# buck.net
KiCad netlist of a schematic drawn in Altium Designer
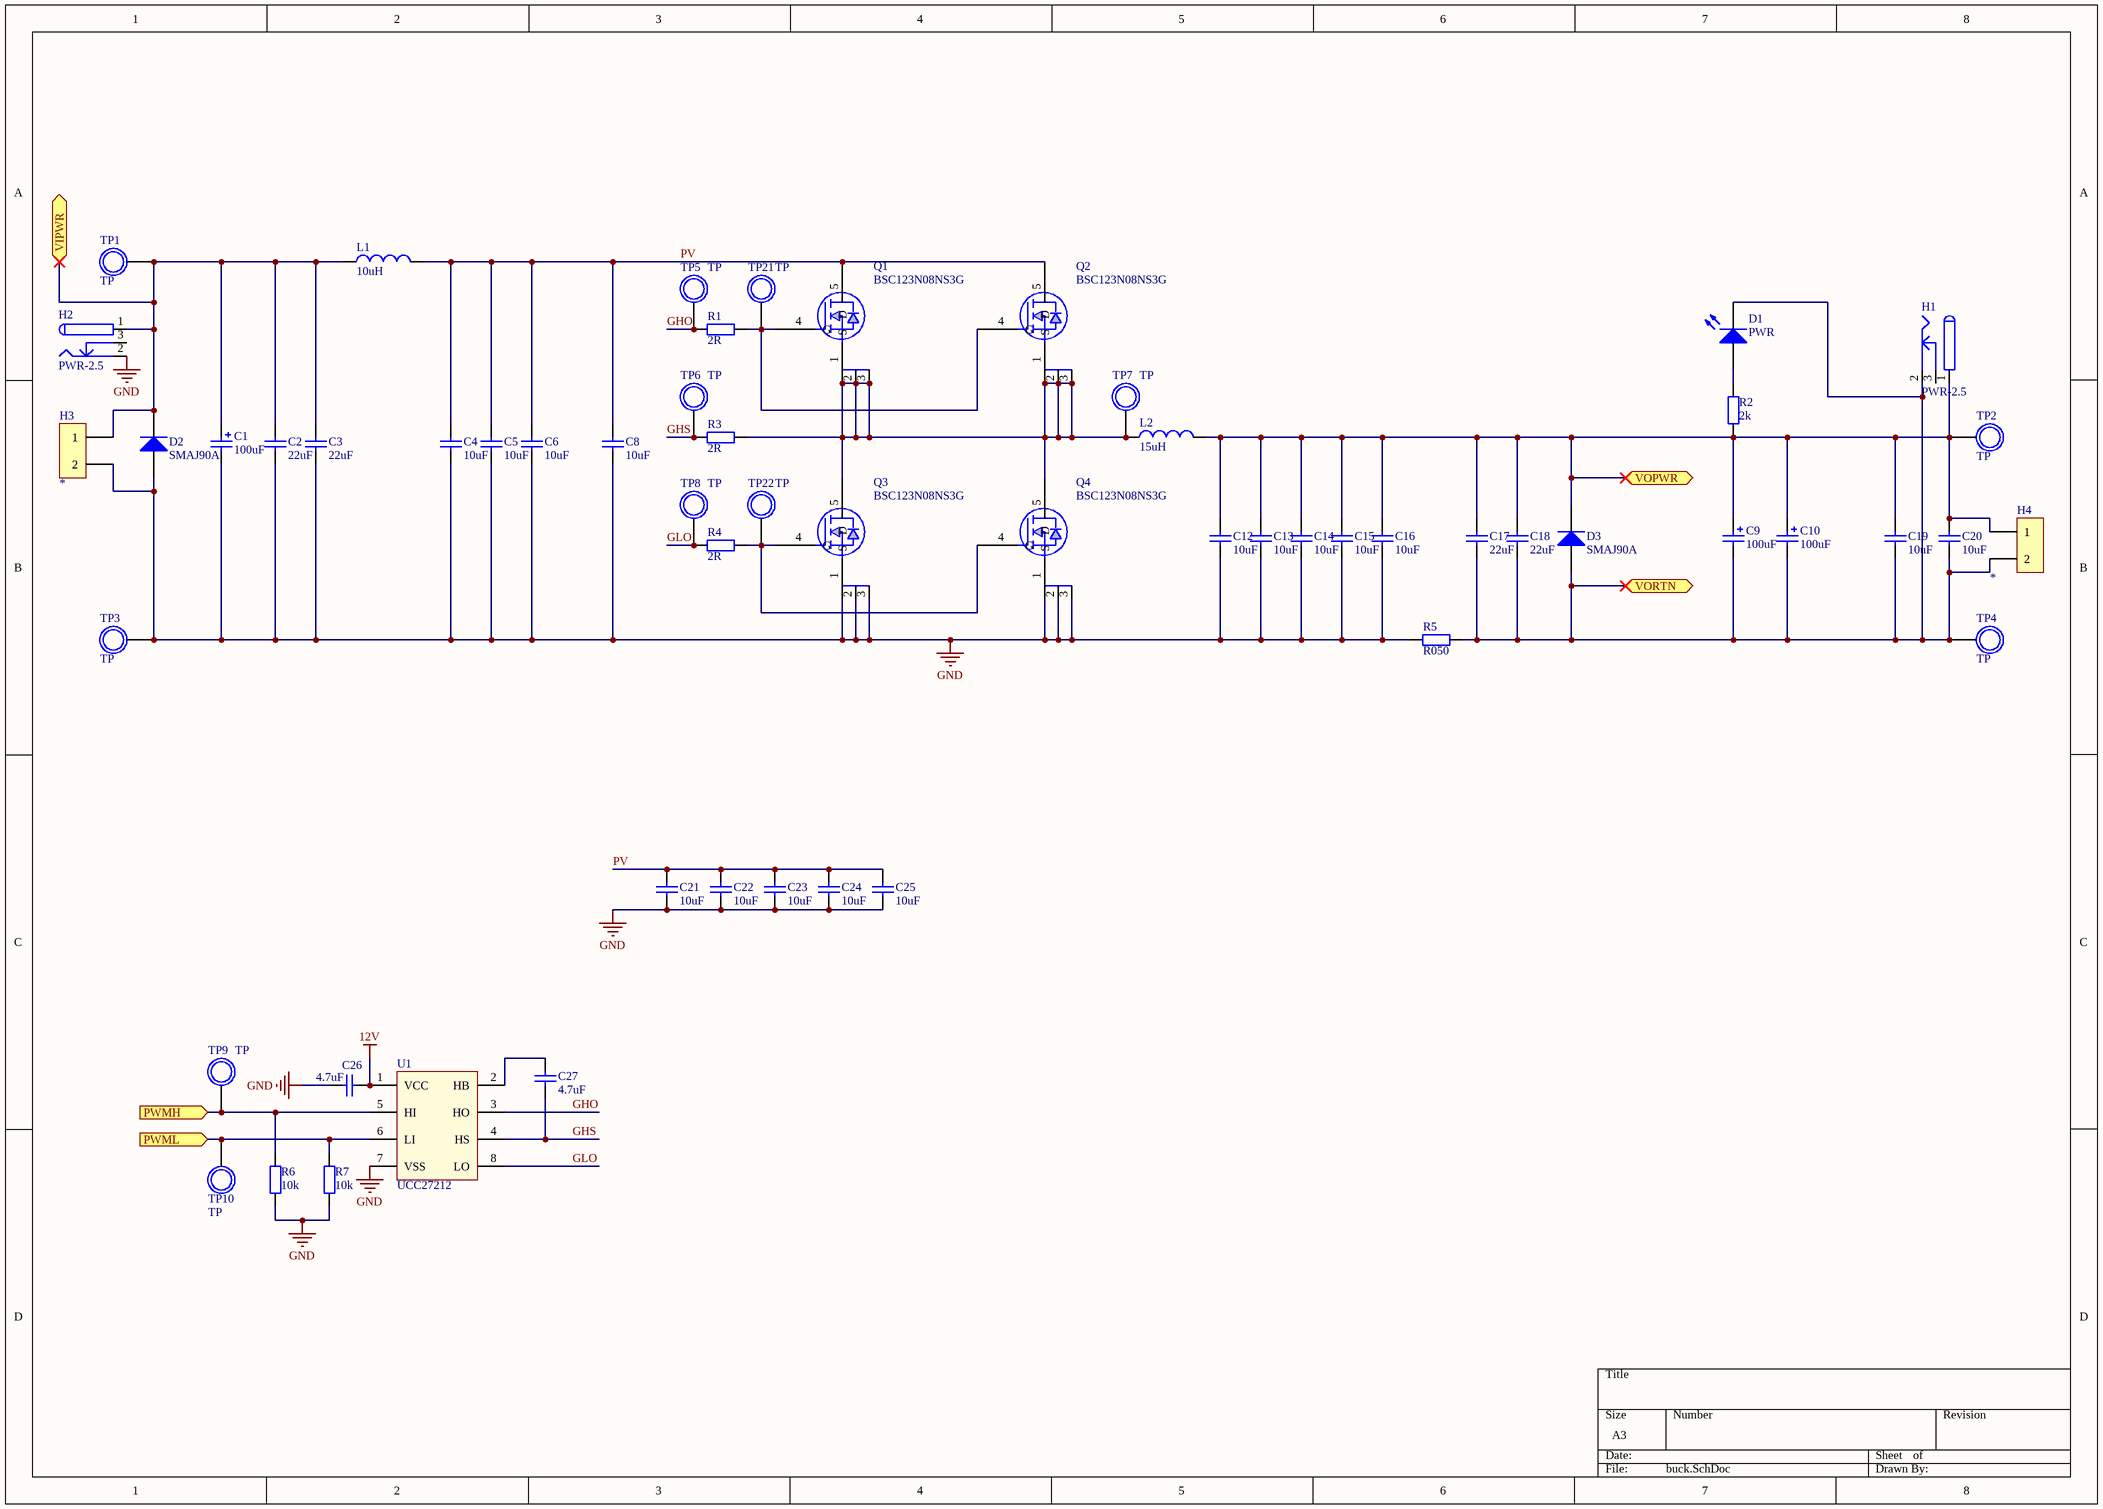
[diagram p0: buck.SchDoc]

(export (version "E")
  (design (tool "Eeschema 10.0.6"))
  (components
    (comp (ref "C1")
      (value "100uF")
      (footprint "CAPAE109103X105N")
      (description "cap pol")
      (fields (field (name "TOLERANCE") "~{+}- 10%"))
      (libsource (lib "PCB_Project") (part "CAP_Pol"))
    )
    (comp (ref "C2")
      (value "22uF")
      (footprint "CAP1206")
      (description "CAP NON-POL")
      (fields (field (name "TOLERANCE") "+/-10%"))
      (libsource (lib "PCB_Project") (part "CAP"))
    )
    (comp (ref "C3")
      (value "22uF")
      (footprint "CAP1206")
      (description "CAP NON-POL")
      (fields (field (name "TOLERANCE") "+/-10%"))
      (libsource (lib "PCB_Project") (part "CAP"))
    )
    (comp (ref "C4")
      (value "10uF")
      (footprint "CAP1206")
      (description "CAP NON-POL")
      (fields (field (name "TOLERANCE") "+/-10%"))
      (libsource (lib "PCB_Project") (part "CAP"))
    )
    (comp (ref "C5")
      (value "10uF")
      (footprint "CAP1206")
      (description "CAP NON-POL")
      (fields (field (name "TOLERANCE") "+/-10%"))
      (libsource (lib "PCB_Project") (part "CAP"))
    )
    (comp (ref "C6")
      (value "10uF")
      (footprint "CAP1206")
      (description "CAP NON-POL")
      (fields (field (name "TOLERANCE") "+/-10%"))
      (libsource (lib "PCB_Project") (part "CAP"))
    )
    (comp (ref "C8")
      (value "10uF")
      (footprint "CAP1206")
      (description "CAP NON-POL")
      (fields (field (name "TOLERANCE") "+/-10%"))
      (libsource (lib "PCB_Project") (part "CAP"))
    )
    (comp (ref "C9")
      (value "100uF")
      (footprint "CAPAE109103X105N")
      (description "cap pol")
      (fields (field (name "TOLERANCE") "~{+}- 10%"))
      (libsource (lib "PCB_Project") (part "CAP_Pol"))
    )
    (comp (ref "C10")
      (value "100uF")
      (footprint "CAPAE109103X105N")
      (description "cap pol")
      (fields (field (name "TOLERANCE") "~{+}- 10%"))
      (libsource (lib "PCB_Project") (part "CAP_Pol"))
    )
    (comp (ref "C12")
      (value "10uF")
      (footprint "CAP1206")
      (description "CAP NON-POL")
      (fields (field (name "TOLERANCE") "+/-10%"))
      (libsource (lib "PCB_Project") (part "CAP"))
    )
    (comp (ref "C13")
      (value "10uF")
      (footprint "CAP1206")
      (description "CAP NON-POL")
      (fields (field (name "TOLERANCE") "+/-10%"))
      (libsource (lib "PCB_Project") (part "CAP"))
    )
    (comp (ref "C14")
      (value "10uF")
      (footprint "CAP1206")
      (description "CAP NON-POL")
      (fields (field (name "TOLERANCE") "+/-10%"))
      (libsource (lib "PCB_Project") (part "CAP"))
    )
    (comp (ref "C15")
      (value "10uF")
      (footprint "CAP1206")
      (description "CAP NON-POL")
      (fields (field (name "TOLERANCE") "+/-10%"))
      (libsource (lib "PCB_Project") (part "CAP"))
    )
    (comp (ref "C16")
      (value "10uF")
      (footprint "CAP1206")
      (description "CAP NON-POL")
      (fields (field (name "TOLERANCE") "+/-10%"))
      (libsource (lib "PCB_Project") (part "CAP"))
    )
    (comp (ref "C17")
      (value "22uF")
      (footprint "CAP1206")
      (description "CAP NON-POL")
      (fields (field (name "TOLERANCE") "+/-10%"))
      (libsource (lib "PCB_Project") (part "CAP"))
    )
    (comp (ref "C18")
      (value "22uF")
      (footprint "CAP1206")
      (description "CAP NON-POL")
      (fields (field (name "TOLERANCE") "+/-10%"))
      (libsource (lib "PCB_Project") (part "CAP"))
    )
    (comp (ref "C19")
      (value "10uF")
      (footprint "CAP1206")
      (description "CAP NON-POL")
      (fields (field (name "TOLERANCE") "+/-10%"))
      (libsource (lib "PCB_Project") (part "CAP"))
    )
    (comp (ref "C20")
      (value "10uF")
      (footprint "CAP1206")
      (description "CAP NON-POL")
      (fields (field (name "TOLERANCE") "+/-10%"))
      (libsource (lib "PCB_Project") (part "CAP"))
    )
    (comp (ref "C21")
      (value "10uF")
      (footprint "CAP1206")
      (description "CAP NON-POL")
      (fields (field (name "TOLERANCE") "+/-10%"))
      (libsource (lib "PCB_Project") (part "CAP"))
    )
    (comp (ref "C22")
      (value "10uF")
      (footprint "CAP1206")
      (description "CAP NON-POL")
      (fields (field (name "TOLERANCE") "+/-10%"))
      (libsource (lib "PCB_Project") (part "CAP"))
    )
    (comp (ref "C23")
      (value "10uF")
      (footprint "CAP1206")
      (description "CAP NON-POL")
      (fields (field (name "TOLERANCE") "+/-10%"))
      (libsource (lib "PCB_Project") (part "CAP"))
    )
    (comp (ref "C24")
      (value "10uF")
      (footprint "CAP1206")
      (description "CAP NON-POL")
      (fields (field (name "TOLERANCE") "+/-10%"))
      (libsource (lib "PCB_Project") (part "CAP"))
    )
    (comp (ref "C25")
      (value "10uF")
      (footprint "CAP1206")
      (description "CAP NON-POL")
      (fields (field (name "TOLERANCE") "+/-10%"))
      (libsource (lib "PCB_Project") (part "CAP"))
    )
    (comp (ref "C26")
      (value "4.7uF")
      (footprint "CAP1206")
      (description "CAP NON-POL")
      (fields (field (name "TOLERANCE") "+/-10%"))
      (libsource (lib "PCB_Project") (part "CAP"))
    )
    (comp (ref "C27")
      (value "4.7uF")
      (footprint "CAP1206")
      (description "CAP NON-POL")
      (fields (field (name "TOLERANCE") "+/-10%"))
      (libsource (lib "PCB_Project") (part "CAP"))
    )
    (comp (ref "D1")
      (value "PWR")
      (footprint "LED0603")
      (description "led")
      (libsource (lib "PCB_Project") (part "LED"))
    )
    (comp (ref "D2")
      (value "SMAJ90A")
      (footprint "SMA")
      (description "diode")
      (libsource (lib "PCB_Project") (part "Diode"))
    )
    (comp (ref "D3")
      (value "SMAJ90A")
      (footprint "SMA")
      (description "diode")
      (libsource (lib "PCB_Project") (part "Diode"))
    )
    (comp (ref "H1") (value "PWR-2.5") (footprint "PWR-2.5") (libsource (lib "PCB_Project") (part "PWR-2.5")))
    (comp (ref "H2") (value "PWR-2.5") (footprint "PWR-2.5") (libsource (lib "PCB_Project") (part "PWR-2.5")))
    (comp (ref "H3") (value "*") (footprint "KF301") (libsource (lib "PCB_Project") (part "Connector-2P")))
    (comp (ref "H4") (value "*") (footprint "KF301") (libsource (lib "") (part "Connector-2P_1")))
    (comp (ref "L1")
      (value "10uH")
      (footprint "CDRH125")
      (description "Inductor")
      (libsource (lib "PCB_Project") (part "Inductor"))
    )
    (comp (ref "L2")
      (value "15uH")
      (footprint "CDRH125")
      (description "Inductor")
      (libsource (lib "PCB_Project") (part "Inductor"))
    )
    (comp (ref "Q1")
      (value "BSC123N08NS3G")
      (footprint "QFN5x6")
      (description "N Channel MOSFET")
      (libsource (lib "PCB_Project") (part "MOS-N4"))
    )
    (comp (ref "Q2")
      (value "BSC123N08NS3G")
      (footprint "QFN5x6")
      (description "N Channel MOSFET")
      (libsource (lib "PCB_Project") (part "MOS-N4"))
    )
    (comp (ref "Q3")
      (value "BSC123N08NS3G")
      (footprint "QFN5x6")
      (description "N Channel MOSFET")
      (libsource (lib "PCB_Project") (part "MOS-N4"))
    )
    (comp (ref "Q4")
      (value "BSC123N08NS3G")
      (footprint "QFN5x6")
      (description "N Channel MOSFET")
      (libsource (lib "PCB_Project") (part "MOS-N4"))
    )
    (comp (ref "R1")
      (value "2R")
      (footprint "RES1206")
      (description "res")
      (libsource (lib "PCB_Project") (part "RES"))
    )
    (comp (ref "R2")
      (value "2k")
      (footprint "RES0603")
      (description "res")
      (libsource (lib "") (part "RES_1"))
    )
    (comp (ref "R3")
      (value "2R")
      (footprint "RES1206")
      (description "res")
      (libsource (lib "PCB_Project") (part "RES"))
    )
    (comp (ref "R4")
      (value "2R")
      (footprint "RES1206")
      (description "res")
      (libsource (lib "PCB_Project") (part "RES"))
    )
    (comp (ref "R5")
      (value "R050")
      (footprint "RESC6432X07N")
      (description "res")
      (libsource (lib "PCB_Project") (part "RES"))
    )
    (comp (ref "R6")
      (value "10k")
      (footprint "RES0603")
      (description "res")
      (libsource (lib "") (part "RES_1"))
    )
    (comp (ref "R7")
      (value "10k")
      (footprint "RES0603")
      (description "res")
      (libsource (lib "") (part "RES_1"))
    )
    (comp (ref "TP1")
      (value "TP")
      (footprint "PAD85R")
      (description "test point")
      (libsource (lib "PCB_Project") (part "Test_Point"))
    )
    (comp (ref "TP2")
      (value "TP")
      (footprint "PAD85R")
      (description "test point")
      (libsource (lib "PCB_Project") (part "Test_Point"))
    )
    (comp (ref "TP3")
      (value "TP")
      (footprint "PAD85R")
      (description "test point")
      (libsource (lib "PCB_Project") (part "Test_Point"))
    )
    (comp (ref "TP4")
      (value "TP")
      (footprint "PAD85R")
      (description "test point")
      (libsource (lib "PCB_Project") (part "Test_Point"))
    )
    (comp (ref "TP5")
      (value "TP")
      (footprint "PAD85R")
      (description "test point")
      (libsource (lib "PCB_Project") (part "Test_Point"))
    )
    (comp (ref "TP6")
      (value "TP")
      (footprint "PAD85R")
      (description "test point")
      (libsource (lib "PCB_Project") (part "Test_Point"))
    )
    (comp (ref "TP7")
      (value "TP")
      (footprint "PAD85R")
      (description "test point")
      (libsource (lib "PCB_Project") (part "Test_Point"))
    )
    (comp (ref "TP8")
      (value "TP")
      (footprint "PAD85R")
      (description "test point")
      (libsource (lib "PCB_Project") (part "Test_Point"))
    )
    (comp (ref "TP9")
      (value "TP")
      (footprint "PAD85R")
      (description "test point")
      (libsource (lib "PCB_Project") (part "Test_Point"))
    )
    (comp (ref "TP10")
      (value "TP")
      (footprint "PAD85R")
      (description "test point")
      (libsource (lib "PCB_Project") (part "Test_Point"))
    )
    (comp (ref "TP21")
      (value "TP")
      (footprint "PAD85R")
      (description "test point")
      (libsource (lib "PCB_Project") (part "Test_Point"))
    )
    (comp (ref "TP22")
      (value "TP")
      (footprint "PAD85R")
      (description "test point")
      (libsource (lib "PCB_Project") (part "Test_Point"))
    )
    (comp (ref "U1")
      (value "UCC27212")
      (footprint "SOP127P600X175-8N")
      (description "UCC2721x 120-V Boot, 4-A Peak, High-Frequency High-Side and Low-Side Driver")
      (libsource (lib "PCB_Project") (part "UCC27211"))
    )
  )
  (nets
    (net (code "1") (name "/GHO") (class "Default")
      (node (ref "R1") (pin "1") (pinfunction "1_1") (pintype "passive"))
      (node (ref "TP5") (pin "1") (pinfunction "1_1") (pintype "passive"))
      (node (ref "U1") (pin "3") (pinfunction "HO_3") (pintype "passive"))
    )
    (net (code "2") (name "/GHS") (class "Default")
      (node (ref "C27") (pin "1") (pinfunction "1_1") (pintype "passive"))
      (node (ref "R3") (pin "1") (pinfunction "1_1") (pintype "passive"))
      (node (ref "TP6") (pin "1") (pinfunction "1_1") (pintype "passive"))
      (node (ref "U1") (pin "4") (pinfunction "HS_4") (pintype "passive"))
    )
    (net (code "3") (name "/GLO") (class "Default")
      (node (ref "R4") (pin "1") (pinfunction "1_1") (pintype "passive"))
      (node (ref "TP8") (pin "1") (pinfunction "1_1") (pintype "passive"))
      (node (ref "U1") (pin "8") (pinfunction "LO_8") (pintype "passive"))
    )
    (net (code "4") (name "/PV") (class "Default")
      (node (ref "C21") (pin "2") (pinfunction "2_2") (pintype "passive"))
      (node (ref "C22") (pin "2") (pinfunction "2_2") (pintype "passive"))
      (node (ref "C23") (pin "2") (pinfunction "2_2") (pintype "passive"))
      (node (ref "C24") (pin "2") (pinfunction "2_2") (pintype "passive"))
      (node (ref "C25") (pin "2") (pinfunction "2_2") (pintype "passive"))
      (node (ref "C4") (pin "2") (pinfunction "2_2") (pintype "passive"))
      (node (ref "C5") (pin "2") (pinfunction "2_2") (pintype "passive"))
      (node (ref "C6") (pin "2") (pinfunction "2_2") (pintype "passive"))
      (node (ref "C8") (pin "2") (pinfunction "2_2") (pintype "passive"))
      (node (ref "L1") (pin "2") (pinfunction "2_2") (pintype "passive"))
      (node (ref "Q1") (pin "5") (pinfunction "D_5") (pintype "passive"))
      (node (ref "Q2") (pin "5") (pinfunction "D_5") (pintype "passive"))
    )
    (net (code "5") (name "/PWMH") (class "Default")
      (node (ref "R6") (pin "2") (pinfunction "2_2") (pintype "passive"))
      (node (ref "TP9") (pin "1") (pinfunction "1_1") (pintype "passive"))
      (node (ref "U1") (pin "5") (pinfunction "HI_5") (pintype "passive"))
    )
    (net (code "6") (name "/PWML") (class "Default")
      (node (ref "R7") (pin "2") (pinfunction "2_2") (pintype "passive"))
      (node (ref "TP10") (pin "1") (pinfunction "1_1") (pintype "passive"))
      (node (ref "U1") (pin "6") (pinfunction "LI_6") (pintype "passive"))
    )
    (net (code "7") (name "/VIPWR") (class "Default")
      (node (ref "C1") (pin "2") (pinfunction "2_2") (pintype "passive"))
      (node (ref "C2") (pin "2") (pinfunction "2_2") (pintype "passive"))
      (node (ref "C3") (pin "2") (pinfunction "2_2") (pintype "passive"))
      (node (ref "D2") (pin "2") (pinfunction "K_2") (pintype "passive"))
      (node (ref "H2") (pin "1") (pinfunction "1_1") (pintype "power_in"))
      (node (ref "H3") (pin "1") (pinfunction "1_1") (pintype "passive"))
      (node (ref "L1") (pin "1") (pinfunction "1_1") (pintype "passive"))
      (node (ref "TP1") (pin "1") (pinfunction "1_1") (pintype "passive"))
    )
    (net (code "8") (name "/VOPWR") (class "Default")
      (node (ref "C10") (pin "2") (pinfunction "2_2") (pintype "passive"))
      (node (ref "C12") (pin "2") (pinfunction "2_2") (pintype "passive"))
      (node (ref "C13") (pin "2") (pinfunction "2_2") (pintype "passive"))
      (node (ref "C14") (pin "2") (pinfunction "2_2") (pintype "passive"))
      (node (ref "C15") (pin "2") (pinfunction "2_2") (pintype "passive"))
      (node (ref "C16") (pin "2") (pinfunction "2_2") (pintype "passive"))
      (node (ref "C17") (pin "2") (pinfunction "2_2") (pintype "passive"))
      (node (ref "C18") (pin "2") (pinfunction "2_2") (pintype "passive"))
      (node (ref "C19") (pin "2") (pinfunction "2_2") (pintype "passive"))
      (node (ref "C20") (pin "2") (pinfunction "2_2") (pintype "passive"))
      (node (ref "C9") (pin "2") (pinfunction "2_2") (pintype "passive"))
      (node (ref "D3") (pin "2") (pinfunction "K_2") (pintype "passive"))
      (node (ref "H1") (pin "1") (pinfunction "1_1") (pintype "power_in"))
      (node (ref "H4") (pin "1") (pinfunction "1_1") (pintype "passive"))
      (node (ref "L2") (pin "2") (pinfunction "2_2") (pintype "passive"))
      (node (ref "R2") (pin "1") (pinfunction "1_1") (pintype "passive"))
      (node (ref "TP2") (pin "1") (pinfunction "1_1") (pintype "passive"))
    )
    (net (code "9") (name "/VORTN") (class "Default")
      (node (ref "C10") (pin "1") (pinfunction "1_1") (pintype "passive"))
      (node (ref "C17") (pin "1") (pinfunction "1_1") (pintype "passive"))
      (node (ref "C18") (pin "1") (pinfunction "1_1") (pintype "passive"))
      (node (ref "C19") (pin "1") (pinfunction "1_1") (pintype "passive"))
      (node (ref "C20") (pin "1") (pinfunction "1_1") (pintype "passive"))
      (node (ref "C9") (pin "1") (pinfunction "1_1") (pintype "passive"))
      (node (ref "D1") (pin "2") (pinfunction "K_2") (pintype "passive"))
      (node (ref "D3") (pin "1") (pinfunction "A_1") (pintype "passive"))
      (node (ref "H1") (pin "2") (pinfunction "2_2") (pintype "power_in"))
      (node (ref "H4") (pin "2") (pinfunction "2_2") (pintype "passive"))
      (node (ref "R5") (pin "2") (pinfunction "2_2") (pintype "passive"))
      (node (ref "TP4") (pin "1") (pinfunction "1_1") (pintype "passive"))
    )
    (net (code "10") (name "12V") (class "Default")
      (node (ref "C26") (pin "2") (pinfunction "2_2") (pintype "passive"))
      (node (ref "U1") (pin "1") (pinfunction "VCC_1") (pintype "passive"))
    )
    (net (code "11") (name "GND") (class "Default")
      (node (ref "C1") (pin "1") (pinfunction "1_1") (pintype "passive"))
      (node (ref "C12") (pin "1") (pinfunction "1_1") (pintype "passive"))
      (node (ref "C13") (pin "1") (pinfunction "1_1") (pintype "passive"))
      (node (ref "C14") (pin "1") (pinfunction "1_1") (pintype "passive"))
      (node (ref "C15") (pin "1") (pinfunction "1_1") (pintype "passive"))
      (node (ref "C16") (pin "1") (pinfunction "1_1") (pintype "passive"))
      (node (ref "C2") (pin "1") (pinfunction "1_1") (pintype "passive"))
      (node (ref "C21") (pin "1") (pinfunction "1_1") (pintype "passive"))
      (node (ref "C22") (pin "1") (pinfunction "1_1") (pintype "passive"))
      (node (ref "C23") (pin "1") (pinfunction "1_1") (pintype "passive"))
      (node (ref "C24") (pin "1") (pinfunction "1_1") (pintype "passive"))
      (node (ref "C25") (pin "1") (pinfunction "1_1") (pintype "passive"))
      (node (ref "C26") (pin "1") (pinfunction "1_1") (pintype "passive"))
      (node (ref "C3") (pin "1") (pinfunction "1_1") (pintype "passive"))
      (node (ref "C4") (pin "1") (pinfunction "1_1") (pintype "passive"))
      (node (ref "C5") (pin "1") (pinfunction "1_1") (pintype "passive"))
      (node (ref "C6") (pin "1") (pinfunction "1_1") (pintype "passive"))
      (node (ref "C8") (pin "1") (pinfunction "1_1") (pintype "passive"))
      (node (ref "D2") (pin "1") (pinfunction "A_1") (pintype "passive"))
      (node (ref "H2") (pin "2") (pinfunction "2_2") (pintype "power_in"))
      (node (ref "H3") (pin "2") (pinfunction "2_2") (pintype "passive"))
      (node (ref "Q3") (pin "1") (pinfunction "S_1") (pintype "passive"))
      (node (ref "Q3") (pin "2") (pintype "passive"))
      (node (ref "Q3") (pin "3") (pintype "passive"))
      (node (ref "Q4") (pin "1") (pinfunction "S_1") (pintype "passive"))
      (node (ref "Q4") (pin "2") (pintype "passive"))
      (node (ref "Q4") (pin "3") (pintype "passive"))
      (node (ref "R5") (pin "1") (pinfunction "1_1") (pintype "passive"))
      (node (ref "R6") (pin "1") (pinfunction "1_1") (pintype "passive"))
      (node (ref "R7") (pin "1") (pinfunction "1_1") (pintype "passive"))
      (node (ref "TP3") (pin "1") (pinfunction "1_1") (pintype "passive"))
      (node (ref "U1") (pin "7") (pinfunction "VSS_7") (pintype "passive"))
    )
    (net (code "12") (name "Net-(D1-A)") (class "Default")
      (node (ref "D1") (pin "1") (pinfunction "A_1") (pintype "passive"))
      (node (ref "R2") (pin "2") (pinfunction "2_2") (pintype "passive"))
    )
    (net (code "13") (name "Net-(Q1-G)") (class "Default")
      (node (ref "Q1") (pin "4") (pinfunction "G_4") (pintype "passive"))
      (node (ref "Q2") (pin "4") (pinfunction "G_4") (pintype "passive"))
      (node (ref "R1") (pin "2") (pinfunction "2_2") (pintype "passive"))
      (node (ref "TP21") (pin "1") (pinfunction "1_1") (pintype "passive"))
    )
    (net (code "14") (name "Net-(Q1-S)") (class "Default")
      (node (ref "L2") (pin "1") (pinfunction "1_1") (pintype "passive"))
      (node (ref "Q1") (pin "1") (pinfunction "S_1") (pintype "passive"))
      (node (ref "Q1") (pin "2") (pintype "passive"))
      (node (ref "Q1") (pin "3") (pintype "passive"))
      (node (ref "Q2") (pin "1") (pinfunction "S_1") (pintype "passive"))
      (node (ref "Q2") (pin "2") (pintype "passive"))
      (node (ref "Q2") (pin "3") (pintype "passive"))
      (node (ref "Q3") (pin "5") (pinfunction "D_5") (pintype "passive"))
      (node (ref "Q4") (pin "5") (pinfunction "D_5") (pintype "passive"))
      (node (ref "R3") (pin "2") (pinfunction "2_2") (pintype "passive"))
      (node (ref "TP7") (pin "1") (pinfunction "1_1") (pintype "passive"))
    )
    (net (code "15") (name "Net-(Q3-G)") (class "Default")
      (node (ref "Q3") (pin "4") (pinfunction "G_4") (pintype "passive"))
      (node (ref "Q4") (pin "4") (pinfunction "G_4") (pintype "passive"))
      (node (ref "R4") (pin "2") (pinfunction "2_2") (pintype "passive"))
      (node (ref "TP22") (pin "1") (pinfunction "1_1") (pintype "passive"))
    )
    (net (code "16") (name "Net-(U1-HB)") (class "Default")
      (node (ref "C27") (pin "2") (pinfunction "2_2") (pintype "passive"))
      (node (ref "U1") (pin "2") (pinfunction "HB_2") (pintype "passive"))
    )
    (net (code "17") (name "unconnected-(H1-Pad3)") (class "Default")
      (node (ref "H1") (pin "3") (pinfunction "3_3") (pintype "power_in"))
    )
    (net (code "18") (name "unconnected-(H2-Pad3)") (class "Default")
      (node (ref "H2") (pin "3") (pinfunction "3_3") (pintype "power_in"))
    )
  )
)
